# 555_Timer_Schematic.net
KiCad netlist of a schematic drawn in Altium Designer
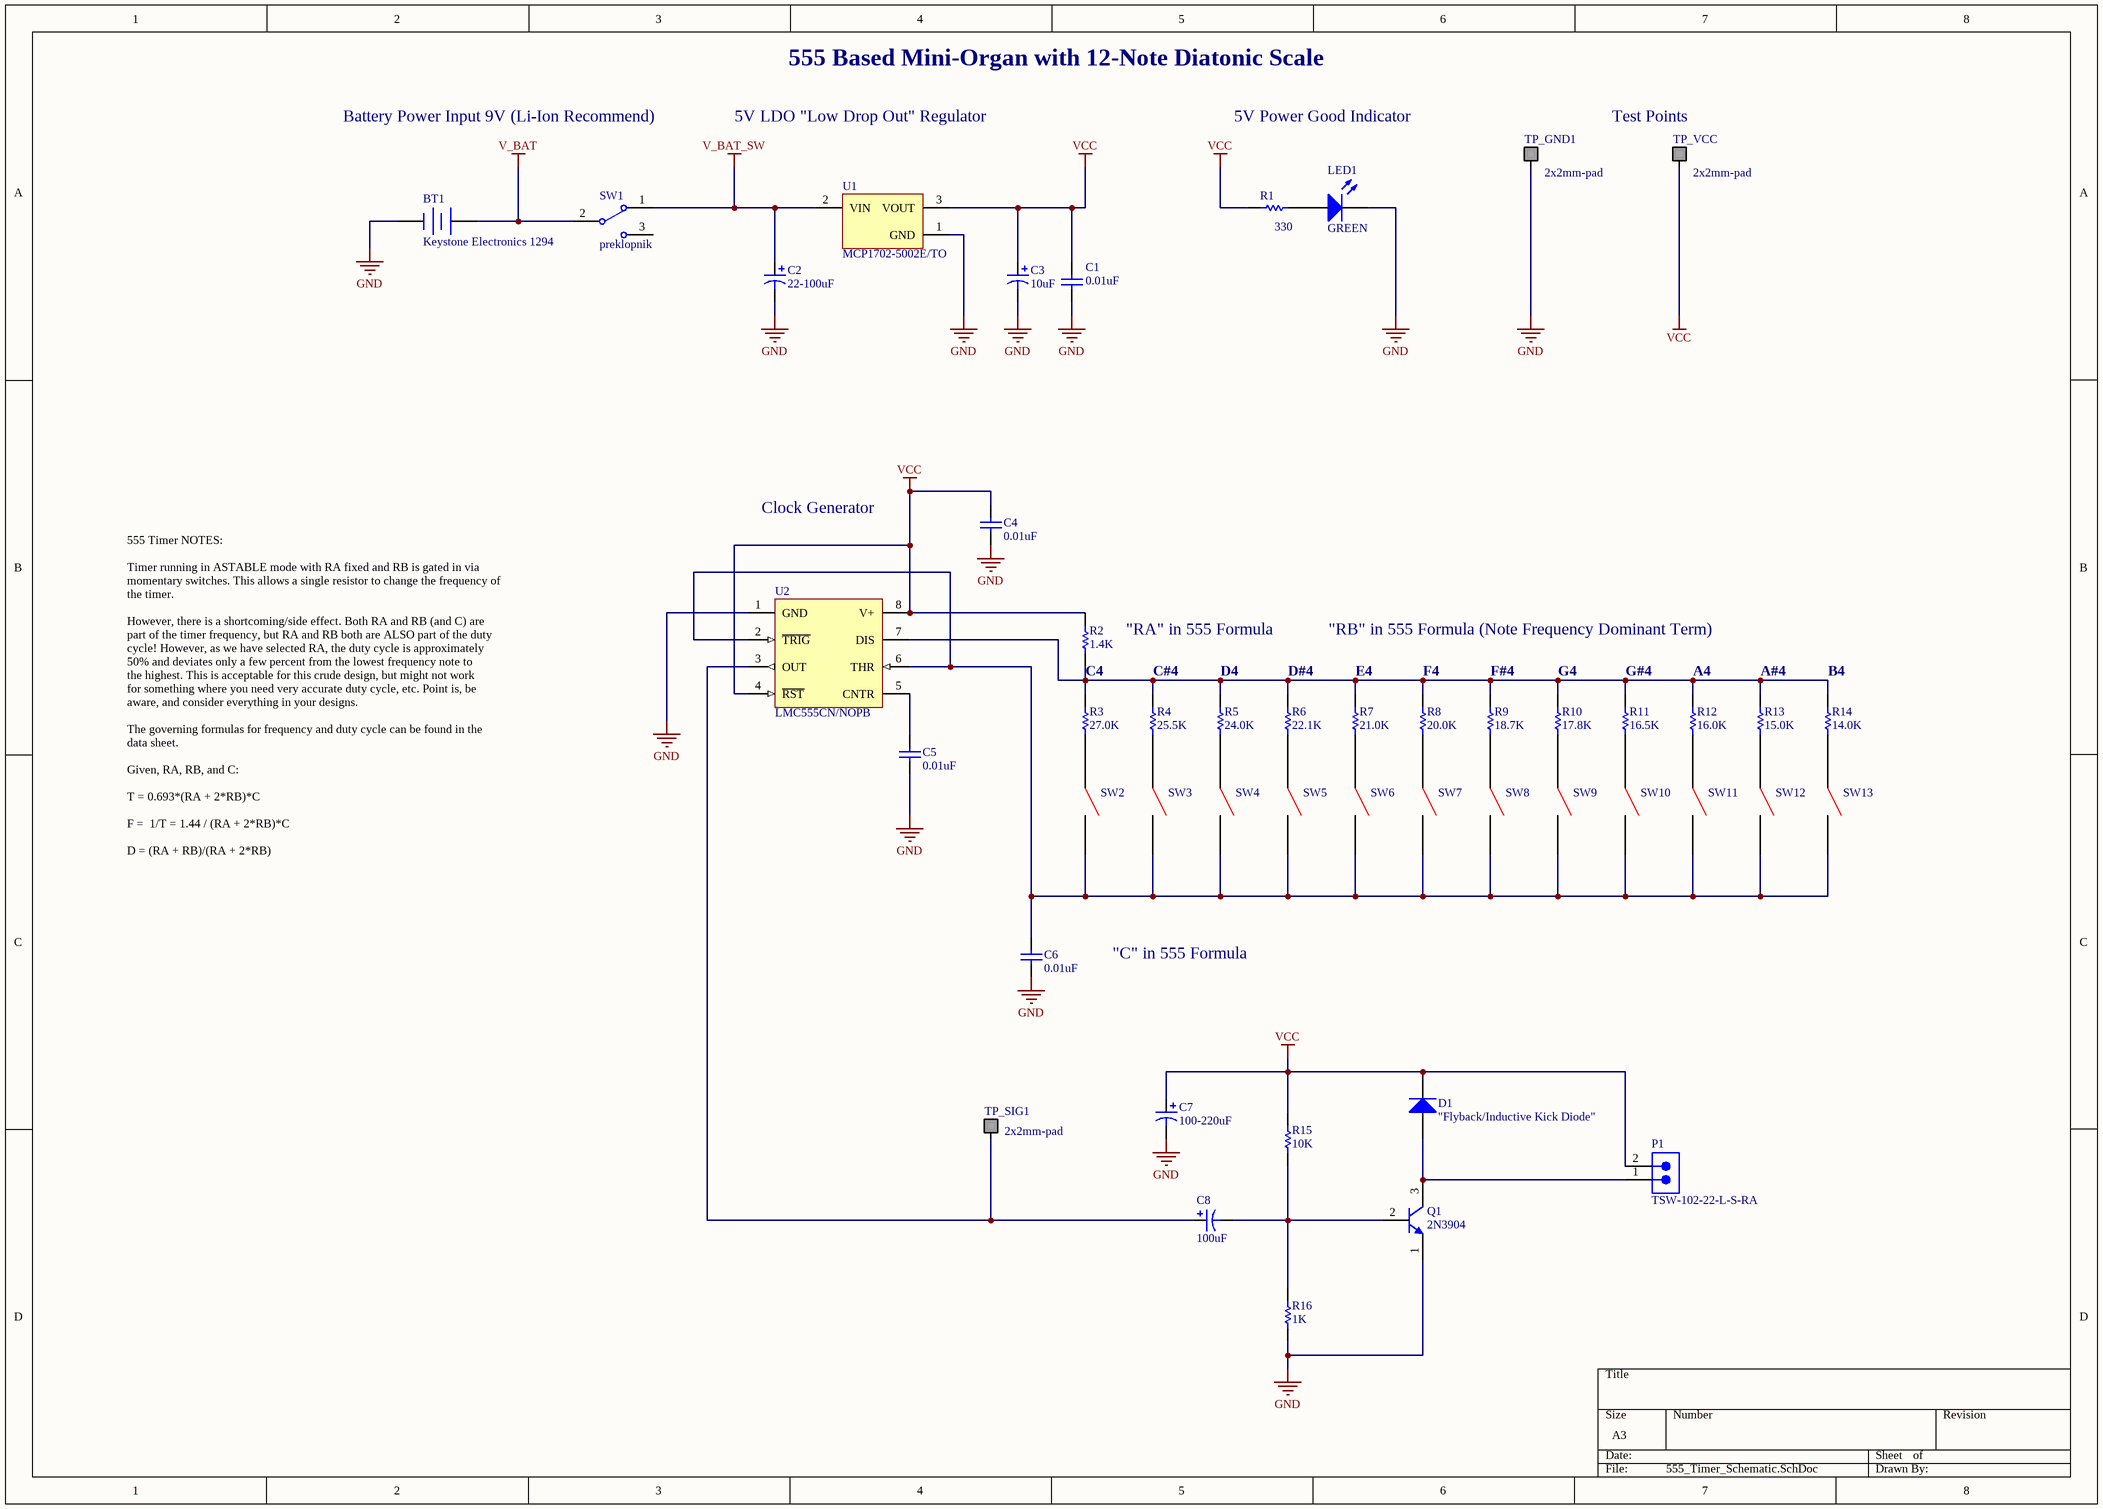
[diagram p0: 555_Timer_Schematic.SchDoc]

(export (version "E")
  (design (tool "Eeschema 10.0.6"))
  (components
    (comp (ref "BT1")
      (value "Keystone Electronics 1294")
      (footprint "PCB-3798-1")
      (description "HOLDER BATT 9V UNIV PLASTIC PC")
      (fields (field (name "MANUFACTURER PART NUMBER") "1294"))
      (libsource (lib "My Personal Space") (part "SYM-3798-1"))
    )
    (comp (ref "C1")
      (value "0.01uF")
      (footprint "PCB-l4zci1ynknckpo24ombh-1")
      (description "Capacitor; Ceramic; Cap 0.1 uF; Tol -20, +80%; Vol-Rtg 50 VDC; Radial; Y5V; Tape & Reel")
      (fields (field (name "MANUFACTURER PART NUMBER") "K104Z15Y5VF5TL2"))
      (libsource (lib "FavoritesLibrary") (part "SYM-7d20b42952c2a2e7-1"))
    )
    (comp (ref "C2")
      (value "22-100uF")
      (footprint "PCB-xswzn1jk2ejoevwvaoxh-1")
      (description "Electrolytic capacitor Radial lead 2.5 mm 10 µF 16 V 20 % (Ø) 4 mm Panasonic EEA-GA1C100H 1 pc(s)")
      (fields (field (name "MANUFACTURER PART NUMBER") "EEA-GA1C100H"))
      (libsource (lib "FavoritesLibrary") (part "SYM-b868704b0d3c67af-1"))
    )
    (comp (ref "C3")
      (value "10uF")
      (footprint "PCB-xswzn1jk2ejoevwvaoxh-1")
      (description "Electrolytic capacitor Radial lead 2.5 mm 10 µF 16 V 20 % (Ø) 4 mm Panasonic EEA-GA1C100H 1 pc(s)")
      (fields (field (name "MANUFACTURER PART NUMBER") "EEA-GA1C100H"))
      (libsource (lib "FavoritesLibrary") (part "SYM-b868704b0d3c67af-1"))
    )
    (comp (ref "C4")
      (value "0.01uF")
      (footprint "PCB-l4zci1ynknckpo24ombh-1")
      (description "Capacitor; Ceramic; Cap 0.1 uF; Tol -20, +80%; Vol-Rtg 50 VDC; Radial; Y5V; Tape & Reel")
      (fields (field (name "MANUFACTURER PART NUMBER") "K104Z15Y5VF5TL2"))
      (libsource (lib "FavoritesLibrary") (part "SYM-7d20b42952c2a2e7-1"))
    )
    (comp (ref "C5")
      (value "0.01uF")
      (footprint "PCB-l4zci1ynknckpo24ombh-1")
      (description "Capacitor; Ceramic; Cap 0.1 uF; Tol -20, +80%; Vol-Rtg 50 VDC; Radial; Y5V; Tape & Reel")
      (fields (field (name "MANUFACTURER PART NUMBER") "K104Z15Y5VF5TL2"))
      (libsource (lib "FavoritesLibrary") (part "SYM-7d20b42952c2a2e7-1"))
    )
    (comp (ref "C6")
      (value "0.01uF")
      (footprint "PCB-l4zci1ynknckpo24ombh-1")
      (description "Capacitor; Ceramic; Cap 0.1 uF; Tol -20, +80%; Vol-Rtg 50 VDC; Radial; Y5V; Tape & Reel")
      (fields (field (name "MANUFACTURER PART NUMBER") "K104Z15Y5VF5TL2"))
      (libsource (lib "FavoritesLibrary") (part "SYM-7d20b42952c2a2e7-1"))
    )
    (comp (ref "C7")
      (value "100-220uF")
      (footprint "PCB-xswzn1jk2ejoevwvaoxh-1")
      (description "Electrolytic capacitor Radial lead 2.5 mm 10 µF 16 V 20 % (Ø) 4 mm Panasonic EEA-GA1C100H 1 pc(s)")
      (fields (field (name "MANUFACTURER PART NUMBER") "EEA-GA1C100H"))
      (libsource (lib "FavoritesLibrary") (part "SYM-b868704b0d3c67af-1"))
    )
    (comp (ref "C8")
      (value "100uF")
      (footprint "PCB-xswzn1jk2ejoevwvaoxh-1")
      (description "Electrolytic capacitor Radial lead 2.5 mm 10 µF 16 V 20 % (Ø) 4 mm Panasonic EEA-GA1C100H 1 pc(s)")
      (fields (field (name "MANUFACTURER PART NUMBER") "EEA-GA1C100H"))
      (libsource (lib "FavoritesLibrary") (part "SYM-b868704b0d3c67af-1"))
    )
    (comp (ref "D1")
      (value "\"Flyback/Inductive Kick Diode\"")
      (footprint "PCB-m243dhbzbg0yyf6dq86g-1")
      (description "1N4001 Series 1 A 400 V Through-Hole Rectifying Diode - DO-41")
      (fields (field (name "MANUFACTURER PART NUMBER") "1N4001-TP"))
      (libsource (lib "Octopart library") (part "SYM-504e994f51a98f89-1"))
    )
    (comp (ref "LED1")
      (value "GREEN")
      (footprint "PCB-teu6t62n2bsx7jl1if62-1")
      (description "LED Uni-Color Green 2-Pin T-1 3/4 Bulk")
      (fields
        (field (name "MANUFACTURER PART NUMBER") "C503B-GCN-CY0C0791")
        (field (name "MANUFACTURER") "Cree")
      )
      (libsource (lib "FavoritesLibrary") (part "SYM-92bb5b2eff764d7c-1"))
    )
    (comp (ref "P1")
      (value "TSW-102-22-L-S-RA")
      (footprint "SMTC-TSW-102-22-X-S-RA")
      (libsource (lib "My Personal Space") (part "SMTC-TSW-102-X-X-S-X"))
    )
    (comp (ref "Q1")
      (value "2N3904")
      (footprint "PCB-z2fqeret6inh8n7vzy86-1")
      (description "Bipolar Transistor, TO-92, 40V, 200mA, NPN")
      (libsource (lib "My Personal Space") (part "ONSC-NPN-B1C2E3-3_C"))
    )
    (comp (ref "R1")
      (value "330")
      (footprint "PCB-bfjjg625tt0lscyu35rt-1")
      (description "Res Carbon Film 1K Ohm 5% 1/4W -400ppm/°C to 0ppm/°C Conformal AXL Thru-Hole T/R")
      (fields (field (name "MANUFACTURER PART NUMBER") "CF14JT1K00"))
      (libsource (lib "FavoritesLibrary") (part "SYM-db3e1311f37e04f9-1"))
    )
    (comp (ref "R2")
      (value "1.4K")
      (footprint "PCB-bfjjg625tt0lscyu35rt-1")
      (description "Res Carbon Film 1K Ohm 5% 1/4W -400ppm/°C to 0ppm/°C Conformal AXL Thru-Hole T/R")
      (fields (field (name "MANUFACTURER PART NUMBER") "CF14JT1K00"))
      (libsource (lib "FavoritesLibrary") (part "SYM-db3e1311f37e04f9-1"))
    )
    (comp (ref "R3")
      (value "27.0K")
      (footprint "PCB-bfjjg625tt0lscyu35rt-1")
      (description "Res Carbon Film 1K Ohm 5% 1/4W -400ppm/°C to 0ppm/°C Conformal AXL Thru-Hole T/R")
      (fields (field (name "MANUFACTURER PART NUMBER") "CF14JT1K00"))
      (libsource (lib "FavoritesLibrary") (part "SYM-db3e1311f37e04f9-1"))
    )
    (comp (ref "R4")
      (value "25.5K")
      (footprint "PCB-bfjjg625tt0lscyu35rt-1")
      (description "Res Carbon Film 1K Ohm 5% 1/4W -400ppm/°C to 0ppm/°C Conformal AXL Thru-Hole T/R")
      (fields (field (name "MANUFACTURER PART NUMBER") "CF14JT1K00"))
      (libsource (lib "FavoritesLibrary") (part "SYM-db3e1311f37e04f9-1"))
    )
    (comp (ref "R5")
      (value "24.0K")
      (footprint "PCB-bfjjg625tt0lscyu35rt-1")
      (description "Res Carbon Film 1K Ohm 5% 1/4W -400ppm/°C to 0ppm/°C Conformal AXL Thru-Hole T/R")
      (fields (field (name "MANUFACTURER PART NUMBER") "CF14JT1K00"))
      (libsource (lib "FavoritesLibrary") (part "SYM-db3e1311f37e04f9-1"))
    )
    (comp (ref "R6")
      (value "22.1K")
      (footprint "PCB-bfjjg625tt0lscyu35rt-1")
      (description "Res Carbon Film 1K Ohm 5% 1/4W -400ppm/°C to 0ppm/°C Conformal AXL Thru-Hole T/R")
      (fields (field (name "MANUFACTURER PART NUMBER") "CF14JT1K00"))
      (libsource (lib "FavoritesLibrary") (part "SYM-db3e1311f37e04f9-1"))
    )
    (comp (ref "R7")
      (value "21.0K")
      (footprint "PCB-bfjjg625tt0lscyu35rt-1")
      (description "Res Carbon Film 1K Ohm 5% 1/4W -400ppm/°C to 0ppm/°C Conformal AXL Thru-Hole T/R")
      (fields (field (name "MANUFACTURER PART NUMBER") "CF14JT1K00"))
      (libsource (lib "FavoritesLibrary") (part "SYM-db3e1311f37e04f9-1"))
    )
    (comp (ref "R8")
      (value "20.0K")
      (footprint "PCB-bfjjg625tt0lscyu35rt-1")
      (description "Res Carbon Film 1K Ohm 5% 1/4W -400ppm/°C to 0ppm/°C Conformal AXL Thru-Hole T/R")
      (fields (field (name "MANUFACTURER PART NUMBER") "CF14JT1K00"))
      (libsource (lib "FavoritesLibrary") (part "SYM-db3e1311f37e04f9-1"))
    )
    (comp (ref "R9")
      (value "18.7K")
      (footprint "PCB-bfjjg625tt0lscyu35rt-1")
      (description "Res Carbon Film 1K Ohm 5% 1/4W -400ppm/°C to 0ppm/°C Conformal AXL Thru-Hole T/R")
      (fields (field (name "MANUFACTURER PART NUMBER") "CF14JT1K00"))
      (libsource (lib "FavoritesLibrary") (part "SYM-db3e1311f37e04f9-1"))
    )
    (comp (ref "R10")
      (value "17.8K")
      (footprint "PCB-bfjjg625tt0lscyu35rt-1")
      (description "Res Carbon Film 1K Ohm 5% 1/4W -400ppm/°C to 0ppm/°C Conformal AXL Thru-Hole T/R")
      (fields (field (name "MANUFACTURER PART NUMBER") "CF14JT1K00"))
      (libsource (lib "FavoritesLibrary") (part "SYM-db3e1311f37e04f9-1"))
    )
    (comp (ref "R11")
      (value "16.5K")
      (footprint "PCB-bfjjg625tt0lscyu35rt-1")
      (description "Res Carbon Film 1K Ohm 5% 1/4W -400ppm/°C to 0ppm/°C Conformal AXL Thru-Hole T/R")
      (fields (field (name "MANUFACTURER PART NUMBER") "CF14JT1K00"))
      (libsource (lib "FavoritesLibrary") (part "SYM-db3e1311f37e04f9-1"))
    )
    (comp (ref "R12")
      (value "16.0K")
      (footprint "PCB-bfjjg625tt0lscyu35rt-1")
      (description "Res Carbon Film 1K Ohm 5% 1/4W -400ppm/°C to 0ppm/°C Conformal AXL Thru-Hole T/R")
      (fields (field (name "MANUFACTURER PART NUMBER") "CF14JT1K00"))
      (libsource (lib "FavoritesLibrary") (part "SYM-db3e1311f37e04f9-1"))
    )
    (comp (ref "R13")
      (value "15.0K")
      (footprint "PCB-bfjjg625tt0lscyu35rt-1")
      (description "Res Carbon Film 1K Ohm 5% 1/4W -400ppm/°C to 0ppm/°C Conformal AXL Thru-Hole T/R")
      (fields (field (name "MANUFACTURER PART NUMBER") "CF14JT1K00"))
      (libsource (lib "FavoritesLibrary") (part "SYM-db3e1311f37e04f9-1"))
    )
    (comp (ref "R14")
      (value "14.0K")
      (footprint "PCB-bfjjg625tt0lscyu35rt-1")
      (description "Res Carbon Film 1K Ohm 5% 1/4W -400ppm/°C to 0ppm/°C Conformal AXL Thru-Hole T/R")
      (fields (field (name "MANUFACTURER PART NUMBER") "CF14JT1K00"))
      (libsource (lib "FavoritesLibrary") (part "SYM-db3e1311f37e04f9-1"))
    )
    (comp (ref "R15")
      (value "10K")
      (footprint "PCB-bfjjg625tt0lscyu35rt-1")
      (description "Res Carbon Film 1K Ohm 5% 1/4W -400ppm/°C to 0ppm/°C Conformal AXL Thru-Hole T/R")
      (fields (field (name "MANUFACTURER PART NUMBER") "CF14JT1K00"))
      (libsource (lib "FavoritesLibrary") (part "SYM-db3e1311f37e04f9-1"))
    )
    (comp (ref "R16")
      (value "1K")
      (footprint "PCB-bfjjg625tt0lscyu35rt-1")
      (description "Res Carbon Film 1K Ohm 5% 1/4W -400ppm/°C to 0ppm/°C Conformal AXL Thru-Hole T/R")
      (fields (field (name "MANUFACTURER PART NUMBER") "CF14JT1K00"))
      (libsource (lib "FavoritesLibrary") (part "SYM-db3e1311f37e04f9-1"))
    )
    (comp (ref "SW1")
      (value "preklopnik")
      (footprint "ESWI-EG1218_V")
      (description "Slide Switch, 500 V, -20 to 70 degC, 3-Pin THD, RoHS")
      (fields (field (name "MANUFACTURER PART NUMBER") "EG1218"))
      (libsource (lib "My Personal Space") (part "SW-SPDT-3"))
    )
    (comp (ref "SW2")
      (value "Panasonic EVQ-21405R")
      (footprint "PCB-je10m8m3eogq13l465bo-1")
      (description "Switch Tactile N.O. SPST Round Button PC Pins 0.02A 15VDC 1.3N Thru-Hole Radial T/R")
      (fields (field (name "ELEMENT14 PART NO.") "2281982"))
      (libsource (lib "Octopart library") (part "SYM-2fe5e5be239cf022-1"))
    )
    (comp (ref "SW3")
      (value "Panasonic EVQ-21405R")
      (footprint "PCB-je10m8m3eogq13l465bo-1")
      (description "Switch Tactile N.O. SPST Round Button PC Pins 0.02A 15VDC 1.3N Thru-Hole Radial T/R")
      (fields (field (name "ELEMENT14 PART NO.") "2281982"))
      (libsource (lib "Octopart library") (part "SYM-2fe5e5be239cf022-1"))
    )
    (comp (ref "SW4")
      (value "Panasonic EVQ-21405R")
      (footprint "PCB-je10m8m3eogq13l465bo-1")
      (description "Switch Tactile N.O. SPST Round Button PC Pins 0.02A 15VDC 1.3N Thru-Hole Radial T/R")
      (fields (field (name "ELEMENT14 PART NO.") "2281982"))
      (libsource (lib "Octopart library") (part "SYM-2fe5e5be239cf022-1"))
    )
    (comp (ref "SW5")
      (value "Panasonic EVQ-21405R")
      (footprint "PCB-je10m8m3eogq13l465bo-1")
      (description "Switch Tactile N.O. SPST Round Button PC Pins 0.02A 15VDC 1.3N Thru-Hole Radial T/R")
      (fields (field (name "ELEMENT14 PART NO.") "2281982"))
      (libsource (lib "Octopart library") (part "SYM-2fe5e5be239cf022-1"))
    )
    (comp (ref "SW6")
      (value "Panasonic EVQ-21405R")
      (footprint "PCB-je10m8m3eogq13l465bo-1")
      (description "Switch Tactile N.O. SPST Round Button PC Pins 0.02A 15VDC 1.3N Thru-Hole Radial T/R")
      (fields (field (name "ELEMENT14 PART NO.") "2281982"))
      (libsource (lib "Octopart library") (part "SYM-2fe5e5be239cf022-1"))
    )
    (comp (ref "SW7")
      (value "Panasonic EVQ-21405R")
      (footprint "PCB-je10m8m3eogq13l465bo-1")
      (description "Switch Tactile N.O. SPST Round Button PC Pins 0.02A 15VDC 1.3N Thru-Hole Radial T/R")
      (fields (field (name "ELEMENT14 PART NO.") "2281982"))
      (libsource (lib "Octopart library") (part "SYM-2fe5e5be239cf022-1"))
    )
    (comp (ref "SW8")
      (value "Panasonic EVQ-21405R")
      (footprint "PCB-je10m8m3eogq13l465bo-1")
      (description "Switch Tactile N.O. SPST Round Button PC Pins 0.02A 15VDC 1.3N Thru-Hole Radial T/R")
      (fields (field (name "ELEMENT14 PART NO.") "2281982"))
      (libsource (lib "Octopart library") (part "SYM-2fe5e5be239cf022-1"))
    )
    (comp (ref "SW9")
      (value "Panasonic EVQ-21405R")
      (footprint "PCB-je10m8m3eogq13l465bo-1")
      (description "Switch Tactile N.O. SPST Round Button PC Pins 0.02A 15VDC 1.3N Thru-Hole Radial T/R")
      (fields (field (name "ELEMENT14 PART NO.") "2281982"))
      (libsource (lib "Octopart library") (part "SYM-2fe5e5be239cf022-1"))
    )
    (comp (ref "SW10")
      (value "Panasonic EVQ-21405R")
      (footprint "PCB-je10m8m3eogq13l465bo-1")
      (description "Switch Tactile N.O. SPST Round Button PC Pins 0.02A 15VDC 1.3N Thru-Hole Radial T/R")
      (fields (field (name "ELEMENT14 PART NO.") "2281982"))
      (libsource (lib "Octopart library") (part "SYM-2fe5e5be239cf022-1"))
    )
    (comp (ref "SW11")
      (value "Panasonic EVQ-21405R")
      (footprint "PCB-je10m8m3eogq13l465bo-1")
      (description "Switch Tactile N.O. SPST Round Button PC Pins 0.02A 15VDC 1.3N Thru-Hole Radial T/R")
      (fields (field (name "ELEMENT14 PART NO.") "2281982"))
      (libsource (lib "Octopart library") (part "SYM-2fe5e5be239cf022-1"))
    )
    (comp (ref "SW12")
      (value "Panasonic EVQ-21405R")
      (footprint "PCB-je10m8m3eogq13l465bo-1")
      (description "Switch Tactile N.O. SPST Round Button PC Pins 0.02A 15VDC 1.3N Thru-Hole Radial T/R")
      (fields (field (name "ELEMENT14 PART NO.") "2281982"))
      (libsource (lib "Octopart library") (part "SYM-2fe5e5be239cf022-1"))
    )
    (comp (ref "SW13")
      (value "Panasonic EVQ-21405R")
      (footprint "PCB-je10m8m3eogq13l465bo-1")
      (description "Switch Tactile N.O. SPST Round Button PC Pins 0.02A 15VDC 1.3N Thru-Hole Radial T/R")
      (fields (field (name "ELEMENT14 PART NO.") "2281982"))
      (libsource (lib "Octopart library") (part "SYM-2fe5e5be239cf022-1"))
    )
    (comp (ref "TP_GND1")
      (value "2x2mm-pad")
      (footprint "PCB-iek5qk9ganu4yn12lo6h-1")
      (description "Raychem; SMT Circuit probe pad, 0805, 0R0 RCT")
      (libsource (lib "Octopart library") (part "SYM-da21135b2be305e6-1"))
    )
    (comp (ref "TP_SIG1")
      (value "2x2mm-pad")
      (footprint "PCB-iek5qk9ganu4yn12lo6h-1")
      (description "Raychem; SMT Circuit probe pad, 0805, 0R0 RCT")
      (libsource (lib "Octopart library") (part "SYM-da21135b2be305e6-1"))
    )
    (comp (ref "TP_VCC")
      (value "2x2mm-pad")
      (footprint "PCB-iek5qk9ganu4yn12lo6h-1")
      (description "Raychem; SMT Circuit probe pad, 0805, 0R0 RCT")
      (libsource (lib "Octopart library") (part "SYM-da21135b2be305e6-1"))
    )
    (comp (ref "U1")
      (value "MCP1702-5002E/TO")
      (footprint "TO-92-TO3")
      (description "250 mA Low Quiescent Current LDO Regulator, 3-Pin TO-92, Extended TemperatureBAG")
      (libsource (lib "My Personal Space") (part "PM-LINEREG-MCP1702-IL3A"))
    )
    (comp (ref "U2")
      (value "LMC555CN/NOPB")
      (footprint "N08E")
      (description "CMOS Timer, 8-pin MDIP, Pb-Free")
      (libsource (lib "FavoritesLibrary") (part "AN-TIMER-LMC555-8"))
    )
  )
  (nets
    (net (code "1") (name "GND") (class "Default")
      (node (ref "BT1") (pin "2") (pinfunction "-_2") (pintype "passive"))
      (node (ref "C1") (pin "2") (pinfunction "2_2") (pintype "passive"))
      (node (ref "C2") (pin "-") (pinfunction "-_-") (pintype "passive"))
      (node (ref "C3") (pin "-") (pinfunction "-_-") (pintype "passive"))
      (node (ref "C4") (pin "2") (pinfunction "2_2") (pintype "passive"))
      (node (ref "C5") (pin "2") (pinfunction "2_2") (pintype "passive"))
      (node (ref "C6") (pin "2") (pinfunction "2_2") (pintype "passive"))
      (node (ref "C7") (pin "-") (pinfunction "-_-") (pintype "passive"))
      (node (ref "LED1") (pin "1") (pinfunction "K_1") (pintype "passive"))
      (node (ref "Q1") (pin "1") (pinfunction "E_1") (pintype "passive"))
      (node (ref "R16") (pin "1") (pinfunction "1_1") (pintype "passive"))
      (node (ref "TP_GND1") (pin "1") (pinfunction "1_1") (pintype "passive"))
      (node (ref "U1") (pin "1") (pinfunction "GND_1") (pintype "power_in"))
      (node (ref "U2") (pin "1") (pinfunction "GND_1") (pintype "power_in"))
    )
    (net (code "2") (name "Net-(D1-A)") (class "Default")
      (node (ref "D1") (pin "1") (pinfunction "A_1") (pintype "passive"))
      (node (ref "P1") (pin "1") (pinfunction "1_1") (pintype "passive"))
      (node (ref "Q1") (pin "3") (pinfunction "C_3") (pintype "passive"))
    )
    (net (code "3") (name "Net-(LED1-A)") (class "Default")
      (node (ref "LED1") (pin "2") (pinfunction "A_2") (pintype "passive"))
      (node (ref "R1") (pin "1") (pinfunction "1_1") (pintype "passive"))
    )
    (net (code "4") (name "Net-(Q1-B)") (class "Default")
      (node (ref "C8") (pin "-") (pinfunction "-_-") (pintype "passive"))
      (node (ref "Q1") (pin "2") (pinfunction "B_2") (pintype "passive"))
      (node (ref "R15") (pin "1") (pinfunction "1_1") (pintype "passive"))
      (node (ref "R16") (pin "2") (pinfunction "2_2") (pintype "passive"))
    )
    (net (code "5") (name "Net-(R3-Pad1)") (class "Default")
      (node (ref "R3") (pin "1") (pinfunction "1_1") (pintype "passive"))
      (node (ref "SW2") (pin "1") (pinfunction "1_1") (pintype "passive"))
    )
    (net (code "6") (name "Net-(R4-Pad1)") (class "Default")
      (node (ref "R4") (pin "1") (pinfunction "1_1") (pintype "passive"))
      (node (ref "SW3") (pin "1") (pinfunction "1_1") (pintype "passive"))
    )
    (net (code "7") (name "Net-(R5-Pad1)") (class "Default")
      (node (ref "R5") (pin "1") (pinfunction "1_1") (pintype "passive"))
      (node (ref "SW4") (pin "1") (pinfunction "1_1") (pintype "passive"))
    )
    (net (code "8") (name "Net-(R6-Pad1)") (class "Default")
      (node (ref "R6") (pin "1") (pinfunction "1_1") (pintype "passive"))
      (node (ref "SW5") (pin "1") (pinfunction "1_1") (pintype "passive"))
    )
    (net (code "9") (name "Net-(R7-Pad1)") (class "Default")
      (node (ref "R7") (pin "1") (pinfunction "1_1") (pintype "passive"))
      (node (ref "SW6") (pin "1") (pinfunction "1_1") (pintype "passive"))
    )
    (net (code "10") (name "Net-(R8-Pad1)") (class "Default")
      (node (ref "R8") (pin "1") (pinfunction "1_1") (pintype "passive"))
      (node (ref "SW7") (pin "1") (pinfunction "1_1") (pintype "passive"))
    )
    (net (code "11") (name "Net-(R9-Pad1)") (class "Default")
      (node (ref "R9") (pin "1") (pinfunction "1_1") (pintype "passive"))
      (node (ref "SW8") (pin "1") (pinfunction "1_1") (pintype "passive"))
    )
    (net (code "12") (name "Net-(R10-Pad1)") (class "Default")
      (node (ref "R10") (pin "1") (pinfunction "1_1") (pintype "passive"))
      (node (ref "SW9") (pin "1") (pinfunction "1_1") (pintype "passive"))
    )
    (net (code "13") (name "Net-(R11-Pad1)") (class "Default")
      (node (ref "R11") (pin "1") (pinfunction "1_1") (pintype "passive"))
      (node (ref "SW10") (pin "1") (pinfunction "1_1") (pintype "passive"))
    )
    (net (code "14") (name "Net-(R12-Pad1)") (class "Default")
      (node (ref "R12") (pin "1") (pinfunction "1_1") (pintype "passive"))
      (node (ref "SW11") (pin "1") (pinfunction "1_1") (pintype "passive"))
    )
    (net (code "15") (name "Net-(R13-Pad1)") (class "Default")
      (node (ref "R13") (pin "1") (pinfunction "1_1") (pintype "passive"))
      (node (ref "SW12") (pin "1") (pinfunction "1_1") (pintype "passive"))
    )
    (net (code "16") (name "Net-(R14-Pad1)") (class "Default")
      (node (ref "R14") (pin "1") (pinfunction "1_1") (pintype "passive"))
      (node (ref "SW13") (pin "1") (pinfunction "1_1") (pintype "passive"))
    )
    (net (code "17") (name "Net-(U2-CNTR)") (class "Default")
      (node (ref "C5") (pin "1") (pinfunction "1_1") (pintype "passive"))
      (node (ref "U2") (pin "5") (pinfunction "CNTR_5") (pintype "passive"))
    )
    (net (code "18") (name "Net-(U2-DIS)") (class "Default")
      (node (ref "R10") (pin "2") (pinfunction "2_2") (pintype "passive"))
      (node (ref "R11") (pin "2") (pinfunction "2_2") (pintype "passive"))
      (node (ref "R12") (pin "2") (pinfunction "2_2") (pintype "passive"))
      (node (ref "R13") (pin "2") (pinfunction "2_2") (pintype "passive"))
      (node (ref "R14") (pin "2") (pinfunction "2_2") (pintype "passive"))
      (node (ref "R2") (pin "1") (pinfunction "1_1") (pintype "passive"))
      (node (ref "R3") (pin "2") (pinfunction "2_2") (pintype "passive"))
      (node (ref "R4") (pin "2") (pinfunction "2_2") (pintype "passive"))
      (node (ref "R5") (pin "2") (pinfunction "2_2") (pintype "passive"))
      (node (ref "R6") (pin "2") (pinfunction "2_2") (pintype "passive"))
      (node (ref "R7") (pin "2") (pinfunction "2_2") (pintype "passive"))
      (node (ref "R8") (pin "2") (pinfunction "2_2") (pintype "passive"))
      (node (ref "R9") (pin "2") (pinfunction "2_2") (pintype "passive"))
      (node (ref "U2") (pin "7") (pinfunction "DIS_7") (pintype "open_collector"))
    )
    (net (code "19") (name "Net-(U2-OUT)") (class "Default")
      (node (ref "C8") (pin "+") (pinfunction "+_+") (pintype "passive"))
      (node (ref "TP_SIG1") (pin "1") (pinfunction "1_1") (pintype "passive"))
      (node (ref "U2") (pin "3") (pinfunction "OUT_3") (pintype "output"))
    )
    (net (code "20") (name "Net-(U2-THR)") (class "Default")
      (node (ref "C6") (pin "1") (pinfunction "1_1") (pintype "passive"))
      (node (ref "SW10") (pin "2") (pinfunction "2_2") (pintype "passive"))
      (node (ref "SW11") (pin "2") (pinfunction "2_2") (pintype "passive"))
      (node (ref "SW12") (pin "2") (pinfunction "2_2") (pintype "passive"))
      (node (ref "SW13") (pin "2") (pinfunction "2_2") (pintype "passive"))
      (node (ref "SW2") (pin "2") (pinfunction "2_2") (pintype "passive"))
      (node (ref "SW3") (pin "2") (pinfunction "2_2") (pintype "passive"))
      (node (ref "SW4") (pin "2") (pinfunction "2_2") (pintype "passive"))
      (node (ref "SW5") (pin "2") (pinfunction "2_2") (pintype "passive"))
      (node (ref "SW6") (pin "2") (pinfunction "2_2") (pintype "passive"))
      (node (ref "SW7") (pin "2") (pinfunction "2_2") (pintype "passive"))
      (node (ref "SW8") (pin "2") (pinfunction "2_2") (pintype "passive"))
      (node (ref "SW9") (pin "2") (pinfunction "2_2") (pintype "passive"))
      (node (ref "U2") (pin "2") (pinfunction "~{TRIG}_2") (pintype "input"))
      (node (ref "U2") (pin "6") (pinfunction "THR_6") (pintype "input"))
    )
    (net (code "21") (name "VCC") (class "Default")
      (node (ref "C1") (pin "1") (pinfunction "1_1") (pintype "passive"))
      (node (ref "C3") (pin "+") (pinfunction "+_+") (pintype "passive"))
      (node (ref "C4") (pin "1") (pinfunction "1_1") (pintype "passive"))
      (node (ref "C7") (pin "+") (pinfunction "+_+") (pintype "passive"))
      (node (ref "D1") (pin "2") (pinfunction "K_2") (pintype "passive"))
      (node (ref "P1") (pin "2") (pinfunction "2_2") (pintype "passive"))
      (node (ref "R1") (pin "2") (pinfunction "2_2") (pintype "passive"))
      (node (ref "R15") (pin "2") (pinfunction "2_2") (pintype "passive"))
      (node (ref "R2") (pin "2") (pinfunction "2_2") (pintype "passive"))
      (node (ref "TP_VCC") (pin "1") (pinfunction "1_1") (pintype "passive"))
      (node (ref "U1") (pin "3") (pinfunction "VOUT_3") (pintype "power_in"))
      (node (ref "U2") (pin "4") (pinfunction "~{RST}_4") (pintype "input"))
      (node (ref "U2") (pin "8") (pinfunction "V+_8") (pintype "power_in"))
    )
    (net (code "22") (name "V_BAT") (class "Default")
      (node (ref "BT1") (pin "1") (pinfunction "+_1") (pintype "passive"))
      (node (ref "SW1") (pin "2") (pinfunction "COM_2") (pintype "passive"))
    )
    (net (code "23") (name "V_BAT_SW") (class "Default")
      (node (ref "C2") (pin "+") (pinfunction "+_+") (pintype "passive"))
      (node (ref "SW1") (pin "1") (pinfunction "1_1") (pintype "passive"))
      (node (ref "U1") (pin "2") (pinfunction "VIN_2") (pintype "power_in"))
    )
    (net (code "24") (name "unconnected-(SW1-Pad3)") (class "Default")
      (node (ref "SW1") (pin "3") (pinfunction "3_3") (pintype "passive"))
    )
  )
)
